# 8-Bit_Register_State_Output.net
KiCad netlist of a schematic drawn in EAGLE
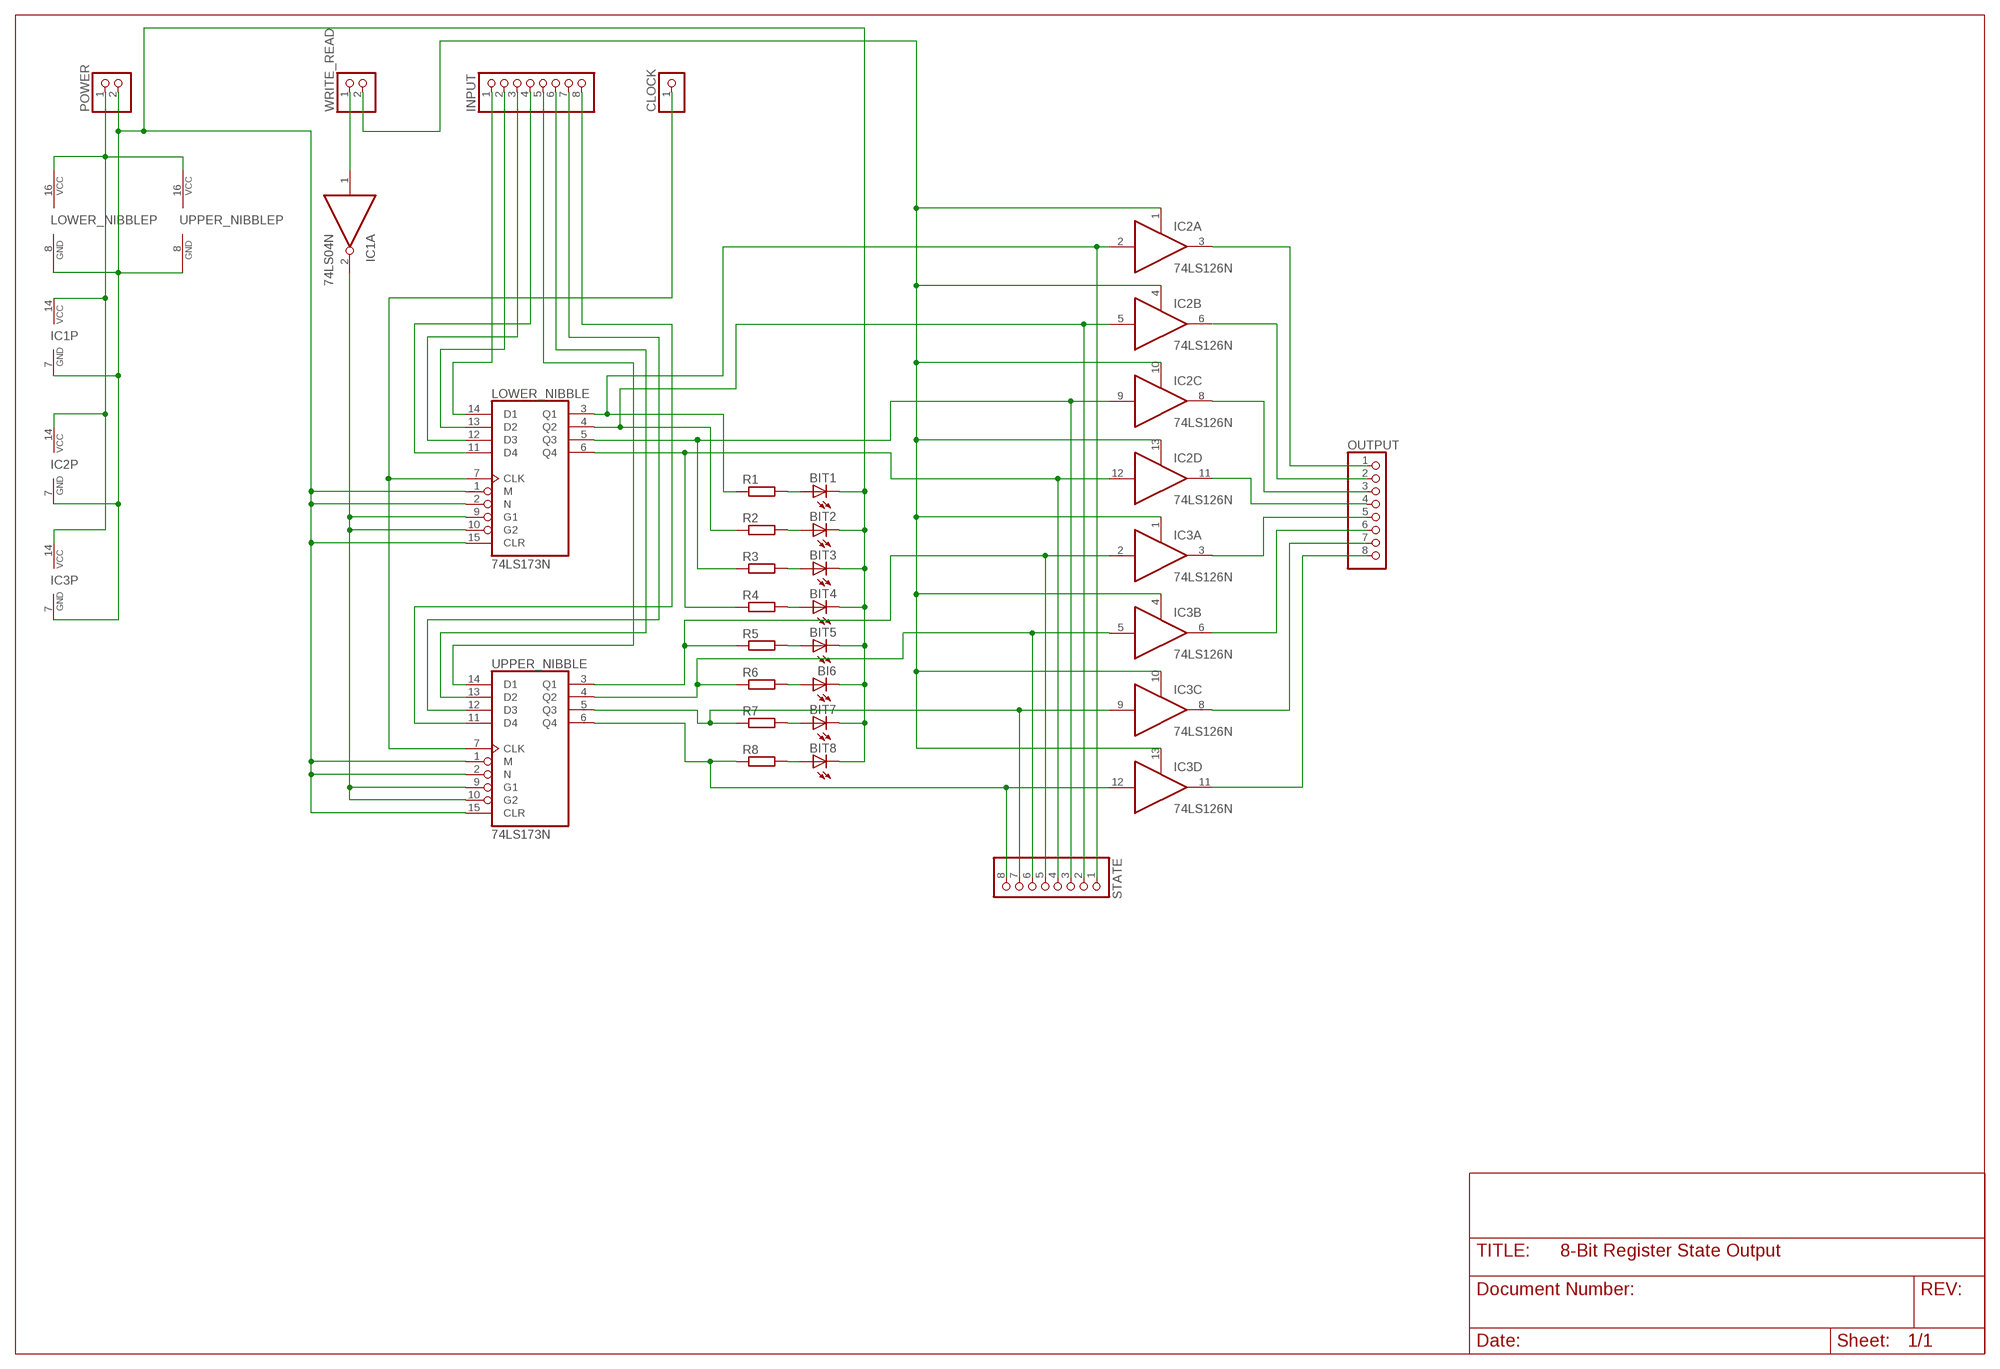
[diagram p0: schematic, sheet 1]

(export (version "E")
  (design (tool "Eeschema 10.0.6"))
  (components
    (comp (ref "BI6")
      (value "LED3MM")
      (footprint "eagle-import:LED3MM")
      (libsource (lib "eagle-import") (part "LED3MM"))
    )
    (comp (ref "BIT1")
      (value "LED3MM")
      (footprint "eagle-import:LED3MM")
      (libsource (lib "eagle-import") (part "LED3MM"))
    )
    (comp (ref "BIT2")
      (value "LED3MM")
      (footprint "eagle-import:LED3MM")
      (libsource (lib "eagle-import") (part "LED3MM"))
    )
    (comp (ref "BIT3")
      (value "LED3MM")
      (footprint "eagle-import:LED3MM")
      (libsource (lib "eagle-import") (part "LED3MM"))
    )
    (comp (ref "BIT4")
      (value "LED3MM")
      (footprint "eagle-import:LED3MM")
      (libsource (lib "eagle-import") (part "LED3MM"))
    )
    (comp (ref "BIT5")
      (value "LED3MM")
      (footprint "eagle-import:LED3MM")
      (libsource (lib "eagle-import") (part "LED3MM"))
    )
    (comp (ref "BIT7")
      (value "LED3MM")
      (footprint "eagle-import:LED3MM")
      (libsource (lib "eagle-import") (part "LED3MM"))
    )
    (comp (ref "BIT8")
      (value "LED3MM")
      (footprint "eagle-import:LED3MM")
      (libsource (lib "eagle-import") (part "LED3MM"))
    )
    (comp (ref "CLOCK")
      (value "PINHD-1X1")
      (footprint "eagle-import:1X01")
      (libsource (lib "eagle-import") (part "PINHD-1X1"))
    )
    (comp (ref "IC1")
      (value "74LS04N")
      (footprint "eagle-import:DIL14")
      (libsource (lib "eagle-import") (part "7404NLS"))
    )
    (comp (ref "IC2")
      (value "74LS126N")
      (footprint "eagle-import:DIL14")
      (libsource (lib "eagle-import") (part "74126NLS"))
    )
    (comp (ref "IC3")
      (value "74LS126N")
      (footprint "eagle-import:DIL14")
      (libsource (lib "eagle-import") (part "74126NLS"))
    )
    (comp (ref "INPUT")
      (value "PINHD-1X8")
      (footprint "eagle-import:1X08")
      (libsource (lib "eagle-import") (part "PINHD-1X8"))
    )
    (comp (ref "LOWER_NIBBLE")
      (value "74LS173N")
      (footprint "eagle-import:DIL16")
      (libsource (lib "eagle-import") (part "74173NLS"))
    )
    (comp (ref "OUTPUT")
      (value "PINHD-1X8")
      (footprint "eagle-import:1X08")
      (libsource (lib "eagle-import") (part "PINHD-1X8"))
    )
    (comp (ref "POWER")
      (value "PINHD-1X2")
      (footprint "eagle-import:1X02")
      (libsource (lib "eagle-import") (part "PINHD-1X2"))
    )
    (comp (ref "R1")
      (value "R-EU_0207/10")
      (footprint "eagle-import:0207_10")
      (libsource (lib "eagle-import") (part "R-EU_0207/10"))
    )
    (comp (ref "R2")
      (value "R-EU_0207/10")
      (footprint "eagle-import:0207_10")
      (libsource (lib "eagle-import") (part "R-EU_0207/10"))
    )
    (comp (ref "R3")
      (value "R-EU_0207/10")
      (footprint "eagle-import:0207_10")
      (libsource (lib "eagle-import") (part "R-EU_0207/10"))
    )
    (comp (ref "R4")
      (value "R-EU_0207/10")
      (footprint "eagle-import:0207_10")
      (libsource (lib "eagle-import") (part "R-EU_0207/10"))
    )
    (comp (ref "R5")
      (value "R-EU_0207/10")
      (footprint "eagle-import:0207_10")
      (libsource (lib "eagle-import") (part "R-EU_0207/10"))
    )
    (comp (ref "R6")
      (value "R-EU_0207/10")
      (footprint "eagle-import:0207_10")
      (libsource (lib "eagle-import") (part "R-EU_0207/10"))
    )
    (comp (ref "R7")
      (value "R-EU_0207/10")
      (footprint "eagle-import:0207_10")
      (libsource (lib "eagle-import") (part "R-EU_0207/10"))
    )
    (comp (ref "R8")
      (value "R-EU_0207/10")
      (footprint "eagle-import:0207_10")
      (libsource (lib "eagle-import") (part "R-EU_0207/10"))
    )
    (comp (ref "STATE")
      (value "PINHD-1X8")
      (footprint "eagle-import:1X08")
      (libsource (lib "eagle-import") (part "PINHD-1X8"))
    )
    (comp (ref "UPPER_NIBBLE")
      (value "74LS173N")
      (footprint "eagle-import:DIL16")
      (libsource (lib "eagle-import") (part "74173NLS"))
    )
    (comp (ref "WRITE_READ")
      (value "PINHD-1X2")
      (footprint "eagle-import:1X02")
      (libsource (lib "eagle-import") (part "PINHD-1X2"))
    )
  )
  (nets
    (net (code "1") (name "Net-(BI6-C)") (class "Default")
      (node (ref "BI6") (pin "K") (pinfunction "C_K") (pintype "passive"))
      (node (ref "BIT1") (pin "K") (pinfunction "C_K") (pintype "passive"))
      (node (ref "BIT2") (pin "K") (pinfunction "C_K") (pintype "passive"))
      (node (ref "BIT3") (pin "K") (pinfunction "C_K") (pintype "passive"))
      (node (ref "BIT4") (pin "K") (pinfunction "C_K") (pintype "passive"))
      (node (ref "BIT5") (pin "K") (pinfunction "C_K") (pintype "passive"))
      (node (ref "BIT7") (pin "K") (pinfunction "C_K") (pintype "passive"))
      (node (ref "BIT8") (pin "K") (pinfunction "C_K") (pintype "passive"))
      (node (ref "IC1") (pin "7") (pinfunction "GND_7") (pintype "power_in"))
      (node (ref "IC2") (pin "7") (pinfunction "GND_7") (pintype "power_in"))
      (node (ref "IC3") (pin "7") (pinfunction "GND_7") (pintype "power_in"))
      (node (ref "LOWER_NIBBLE") (pin "1") (pinfunction "M_1") (pintype "input"))
      (node (ref "LOWER_NIBBLE") (pin "15") (pinfunction "CLR_15") (pintype "input"))
      (node (ref "LOWER_NIBBLE") (pin "2") (pinfunction "N_2") (pintype "input"))
      (node (ref "LOWER_NIBBLE") (pin "8") (pinfunction "GND_8") (pintype "power_in"))
      (node (ref "POWER") (pin "2") (pinfunction "2_2") (pintype "passive"))
      (node (ref "UPPER_NIBBLE") (pin "1") (pinfunction "M_1") (pintype "input"))
      (node (ref "UPPER_NIBBLE") (pin "15") (pinfunction "CLR_15") (pintype "input"))
      (node (ref "UPPER_NIBBLE") (pin "2") (pinfunction "N_2") (pintype "input"))
      (node (ref "UPPER_NIBBLE") (pin "8") (pinfunction "GND_8") (pintype "power_in"))
    )
    (net (code "2") (name "Net-(BI6-PadA)") (class "Default")
      (node (ref "BI6") (pin "A") (pinfunction "A_A") (pintype "passive"))
      (node (ref "R6") (pin "2") (pinfunction "2_2") (pintype "passive"))
    )
    (net (code "3") (name "Net-(BIT1-PadA)") (class "Default")
      (node (ref "BIT1") (pin "A") (pinfunction "A_A") (pintype "passive"))
      (node (ref "R1") (pin "2") (pinfunction "2_2") (pintype "passive"))
    )
    (net (code "4") (name "Net-(BIT2-PadA)") (class "Default")
      (node (ref "BIT2") (pin "A") (pinfunction "A_A") (pintype "passive"))
      (node (ref "R2") (pin "2") (pinfunction "2_2") (pintype "passive"))
    )
    (net (code "5") (name "Net-(BIT3-PadA)") (class "Default")
      (node (ref "BIT3") (pin "A") (pinfunction "A_A") (pintype "passive"))
      (node (ref "R3") (pin "2") (pinfunction "2_2") (pintype "passive"))
    )
    (net (code "6") (name "Net-(BIT4-PadA)") (class "Default")
      (node (ref "BIT4") (pin "A") (pinfunction "A_A") (pintype "passive"))
      (node (ref "R4") (pin "2") (pinfunction "2_2") (pintype "passive"))
    )
    (net (code "7") (name "Net-(BIT5-PadA)") (class "Default")
      (node (ref "BIT5") (pin "A") (pinfunction "A_A") (pintype "passive"))
      (node (ref "R5") (pin "2") (pinfunction "2_2") (pintype "passive"))
    )
    (net (code "8") (name "Net-(BIT7-PadA)") (class "Default")
      (node (ref "BIT7") (pin "A") (pinfunction "A_A") (pintype "passive"))
      (node (ref "R7") (pin "2") (pinfunction "2_2") (pintype "passive"))
    )
    (net (code "9") (name "Net-(BIT8-PadA)") (class "Default")
      (node (ref "BIT8") (pin "A") (pinfunction "A_A") (pintype "passive"))
      (node (ref "R8") (pin "2") (pinfunction "2_2") (pintype "passive"))
    )
    (net (code "10") (name "Net-(IC1A-I)") (class "Default")
      (node (ref "IC1") (pin "1") (pinfunction "I_1") (pintype "input"))
      (node (ref "WRITE_READ") (pin "1") (pinfunction "1_1") (pintype "passive"))
    )
    (net (code "11") (name "Net-(IC1A-O)") (class "Default")
      (node (ref "IC1") (pin "2") (pinfunction "O_2") (pintype "output"))
      (node (ref "LOWER_NIBBLE") (pin "10") (pinfunction "G2_10") (pintype "input"))
      (node (ref "LOWER_NIBBLE") (pin "9") (pinfunction "G1_9") (pintype "input"))
      (node (ref "UPPER_NIBBLE") (pin "10") (pinfunction "G2_10") (pintype "input"))
      (node (ref "UPPER_NIBBLE") (pin "9") (pinfunction "G1_9") (pintype "input"))
    )
    (net (code "12") (name "Net-(IC1G-VCC)") (class "Default")
      (node (ref "IC1") (pin "14") (pinfunction "VCC_14") (pintype "power_in"))
      (node (ref "IC2") (pin "14") (pinfunction "VCC_14") (pintype "power_in"))
      (node (ref "IC3") (pin "14") (pinfunction "VCC_14") (pintype "power_in"))
      (node (ref "LOWER_NIBBLE") (pin "16") (pinfunction "VCC_16") (pintype "power_in"))
      (node (ref "POWER") (pin "1") (pinfunction "1_1") (pintype "passive"))
      (node (ref "UPPER_NIBBLE") (pin "16") (pinfunction "VCC_16") (pintype "power_in"))
    )
    (net (code "13") (name "Net-(IC2A-I)") (class "Default")
      (node (ref "IC2") (pin "2") (pinfunction "I_2") (pintype "input"))
      (node (ref "LOWER_NIBBLE") (pin "3") (pinfunction "Q1_3") (pintype "tri_state"))
      (node (ref "R1") (pin "1") (pinfunction "1_1") (pintype "passive"))
      (node (ref "STATE") (pin "1") (pinfunction "1_1") (pintype "passive"))
    )
    (net (code "14") (name "Net-(IC2A-O)") (class "Default")
      (node (ref "IC2") (pin "3") (pinfunction "O_3") (pintype "output"))
      (node (ref "OUTPUT") (pin "1") (pinfunction "1_1") (pintype "passive"))
    )
    (net (code "15") (name "Net-(IC2A-OE)") (class "Default")
      (node (ref "IC2") (pin "1") (pinfunction "OE_1") (pintype "input"))
      (node (ref "IC2") (pin "10") (pinfunction "OE_10") (pintype "input"))
      (node (ref "IC2") (pin "13") (pinfunction "OE_13") (pintype "input"))
      (node (ref "IC2") (pin "4") (pinfunction "OE_4") (pintype "input"))
      (node (ref "IC3") (pin "1") (pinfunction "OE_1") (pintype "input"))
      (node (ref "IC3") (pin "10") (pinfunction "OE_10") (pintype "input"))
      (node (ref "IC3") (pin "13") (pinfunction "OE_13") (pintype "input"))
      (node (ref "IC3") (pin "4") (pinfunction "OE_4") (pintype "input"))
      (node (ref "WRITE_READ") (pin "2") (pinfunction "2_2") (pintype "passive"))
    )
    (net (code "16") (name "Net-(IC2B-I)") (class "Default")
      (node (ref "IC2") (pin "5") (pinfunction "I_5") (pintype "input"))
      (node (ref "LOWER_NIBBLE") (pin "4") (pinfunction "Q2_4") (pintype "tri_state"))
      (node (ref "R2") (pin "1") (pinfunction "1_1") (pintype "passive"))
      (node (ref "STATE") (pin "2") (pinfunction "2_2") (pintype "passive"))
    )
    (net (code "17") (name "Net-(IC2B-O)") (class "Default")
      (node (ref "IC2") (pin "6") (pinfunction "O_6") (pintype "output"))
      (node (ref "OUTPUT") (pin "2") (pinfunction "2_2") (pintype "passive"))
    )
    (net (code "18") (name "Net-(IC2C-I)") (class "Default")
      (node (ref "IC2") (pin "9") (pinfunction "I_9") (pintype "input"))
      (node (ref "LOWER_NIBBLE") (pin "5") (pinfunction "Q3_5") (pintype "tri_state"))
      (node (ref "R3") (pin "1") (pinfunction "1_1") (pintype "passive"))
      (node (ref "STATE") (pin "3") (pinfunction "3_3") (pintype "passive"))
    )
    (net (code "19") (name "Net-(IC2C-O)") (class "Default")
      (node (ref "IC2") (pin "8") (pinfunction "O_8") (pintype "output"))
      (node (ref "OUTPUT") (pin "3") (pinfunction "3_3") (pintype "passive"))
    )
    (net (code "20") (name "Net-(IC2D-I)") (class "Default")
      (node (ref "IC2") (pin "12") (pinfunction "I_12") (pintype "input"))
      (node (ref "LOWER_NIBBLE") (pin "6") (pinfunction "Q4_6") (pintype "tri_state"))
      (node (ref "R4") (pin "1") (pinfunction "1_1") (pintype "passive"))
      (node (ref "STATE") (pin "4") (pinfunction "4_4") (pintype "passive"))
    )
    (net (code "21") (name "Net-(IC2D-O)") (class "Default")
      (node (ref "IC2") (pin "11") (pinfunction "O_11") (pintype "output"))
      (node (ref "OUTPUT") (pin "4") (pinfunction "4_4") (pintype "passive"))
    )
    (net (code "22") (name "Net-(IC3A-I)") (class "Default")
      (node (ref "IC3") (pin "2") (pinfunction "I_2") (pintype "input"))
      (node (ref "R5") (pin "1") (pinfunction "1_1") (pintype "passive"))
      (node (ref "STATE") (pin "5") (pinfunction "5_5") (pintype "passive"))
      (node (ref "UPPER_NIBBLE") (pin "3") (pinfunction "Q1_3") (pintype "tri_state"))
    )
    (net (code "23") (name "Net-(IC3A-O)") (class "Default")
      (node (ref "IC3") (pin "3") (pinfunction "O_3") (pintype "output"))
      (node (ref "OUTPUT") (pin "5") (pinfunction "5_5") (pintype "passive"))
    )
    (net (code "24") (name "Net-(IC3B-I)") (class "Default")
      (node (ref "IC3") (pin "5") (pinfunction "I_5") (pintype "input"))
      (node (ref "R6") (pin "1") (pinfunction "1_1") (pintype "passive"))
      (node (ref "STATE") (pin "6") (pinfunction "6_6") (pintype "passive"))
      (node (ref "UPPER_NIBBLE") (pin "4") (pinfunction "Q2_4") (pintype "tri_state"))
    )
    (net (code "25") (name "Net-(IC3B-O)") (class "Default")
      (node (ref "IC3") (pin "6") (pinfunction "O_6") (pintype "output"))
      (node (ref "OUTPUT") (pin "6") (pinfunction "6_6") (pintype "passive"))
    )
    (net (code "26") (name "Net-(IC3C-I)") (class "Default")
      (node (ref "IC3") (pin "9") (pinfunction "I_9") (pintype "input"))
      (node (ref "R7") (pin "1") (pinfunction "1_1") (pintype "passive"))
      (node (ref "STATE") (pin "7") (pinfunction "7_7") (pintype "passive"))
      (node (ref "UPPER_NIBBLE") (pin "5") (pinfunction "Q3_5") (pintype "tri_state"))
    )
    (net (code "27") (name "Net-(IC3C-O)") (class "Default")
      (node (ref "IC3") (pin "8") (pinfunction "O_8") (pintype "output"))
      (node (ref "OUTPUT") (pin "7") (pinfunction "7_7") (pintype "passive"))
    )
    (net (code "28") (name "Net-(IC3D-I)") (class "Default")
      (node (ref "IC3") (pin "12") (pinfunction "I_12") (pintype "input"))
      (node (ref "R8") (pin "1") (pinfunction "1_1") (pintype "passive"))
      (node (ref "STATE") (pin "8") (pinfunction "8_8") (pintype "passive"))
      (node (ref "UPPER_NIBBLE") (pin "6") (pinfunction "Q4_6") (pintype "tri_state"))
    )
    (net (code "29") (name "Net-(IC3D-O)") (class "Default")
      (node (ref "IC3") (pin "11") (pinfunction "O_11") (pintype "output"))
      (node (ref "OUTPUT") (pin "8") (pinfunction "8_8") (pintype "passive"))
    )
    (net (code "30") (name "Net-(LOWER_NIBBLEA-CLK)") (class "Default")
      (node (ref "CLOCK") (pin "1") (pinfunction "1_1") (pintype "passive"))
      (node (ref "LOWER_NIBBLE") (pin "7") (pinfunction "CLK_7") (pintype "input"))
      (node (ref "UPPER_NIBBLE") (pin "7") (pinfunction "CLK_7") (pintype "input"))
    )
    (net (code "31") (name "Net-(LOWER_NIBBLEA-D1)") (class "Default")
      (node (ref "INPUT") (pin "1") (pinfunction "1_1") (pintype "passive"))
      (node (ref "LOWER_NIBBLE") (pin "14") (pinfunction "D1_14") (pintype "input"))
    )
    (net (code "32") (name "Net-(LOWER_NIBBLEA-D2)") (class "Default")
      (node (ref "INPUT") (pin "2") (pinfunction "2_2") (pintype "passive"))
      (node (ref "LOWER_NIBBLE") (pin "13") (pinfunction "D2_13") (pintype "input"))
    )
    (net (code "33") (name "Net-(LOWER_NIBBLEA-D3)") (class "Default")
      (node (ref "INPUT") (pin "3") (pinfunction "3_3") (pintype "passive"))
      (node (ref "LOWER_NIBBLE") (pin "12") (pinfunction "D3_12") (pintype "input"))
    )
    (net (code "34") (name "Net-(LOWER_NIBBLEA-D4)") (class "Default")
      (node (ref "INPUT") (pin "4") (pinfunction "4_4") (pintype "passive"))
      (node (ref "LOWER_NIBBLE") (pin "11") (pinfunction "D4_11") (pintype "input"))
    )
    (net (code "35") (name "Net-(UPPER_NIBBLEA-D1)") (class "Default")
      (node (ref "INPUT") (pin "5") (pinfunction "5_5") (pintype "passive"))
      (node (ref "UPPER_NIBBLE") (pin "14") (pinfunction "D1_14") (pintype "input"))
    )
    (net (code "36") (name "Net-(UPPER_NIBBLEA-D2)") (class "Default")
      (node (ref "INPUT") (pin "6") (pinfunction "6_6") (pintype "passive"))
      (node (ref "UPPER_NIBBLE") (pin "13") (pinfunction "D2_13") (pintype "input"))
    )
    (net (code "37") (name "Net-(UPPER_NIBBLEA-D3)") (class "Default")
      (node (ref "INPUT") (pin "7") (pinfunction "7_7") (pintype "passive"))
      (node (ref "UPPER_NIBBLE") (pin "12") (pinfunction "D3_12") (pintype "input"))
    )
    (net (code "38") (name "Net-(UPPER_NIBBLEA-D4)") (class "Default")
      (node (ref "INPUT") (pin "8") (pinfunction "8_8") (pintype "passive"))
      (node (ref "UPPER_NIBBLE") (pin "11") (pinfunction "D4_11") (pintype "input"))
    )
  )
)
